# SerialConverter.net
KiCad netlist of a schematic drawn in Altium Designer
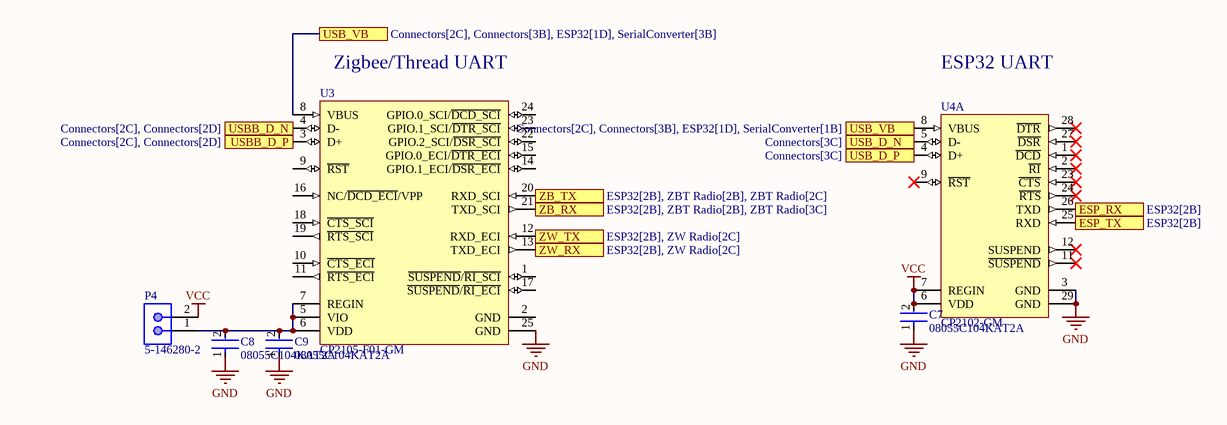
[diagram p0: SerialConverter.SchDoc]

(export (version "E")
  (design (tool "Eeschema 10.0.6"))
  (components
    (comp (ref "C7")
      (value "08055C104KAT2A")
      (footprint "FP-0805-L_2_01_0_2-W_1_25-IPC_C")
      (description "General Purpose Ceramic Capacitor, 0805, 100nF, 10%, X7R, 0.15, 50V")
      (fields (field (name "TOLERANCE") "10%") (field (name "VOLTAGE") "50V"))
      (libsource (lib "Altium Content Vault") (part "02cd4be3c70576c341d710602a673aa"))
    )
    (comp (ref "C8")
      (value "08055C104KAT2A")
      (footprint "FP-0805-L_2_01_0_2-W_1_25-IPC_C")
      (description "General Purpose Ceramic Capacitor, 0805, 100nF, 10%, X7R, 0.15, 50V")
      (fields (field (name "TOLERANCE") "10%") (field (name "VOLTAGE") "50V"))
      (libsource (lib "Altium Content Vault") (part "02cd4be3c70576c341d710602a673aa"))
    )
    (comp (ref "C9")
      (value "08055C104KAT2A")
      (footprint "FP-0805-L_2_01_0_2-W_1_25-IPC_C")
      (description "General Purpose Ceramic Capacitor, 0805, 100nF, 10%, X7R, 0.15, 50V")
      (fields (field (name "TOLERANCE") "10%") (field (name "VOLTAGE") "50V"))
      (libsource (lib "Altium Content Vault") (part "02cd4be3c70576c341d710602a673aa"))
    )
    (comp (ref "P4")
      (value "5-146280-2")
      (footprint "TECO-5-146280-2_V")
      (fields (field (name "MANUFACTURER") "TE Connectivity"))
      (libsource (lib "Altium Content Vault") (part "CN-1P-M-R2"))
    )
    (comp (ref "U3")
      (value "CP2105-F01-GM")
      (footprint "SLAB-QFN-24-2675x2675TP_N")
      (fields (field (name "MANUFACTURER") "Silicon Labs"))
      (libsource (lib "Altium Content Vault") (part "SLAB-CP2105-QFN-24-25"))
    )
    (comp (ref "U4")
      (value "CP2102-GM")
      (footprint "SLAB-QFN-28-3125x3125TP_N")
      (description "Single-Chip USB to UART Bridge, 1024 Bytes EEPROM, -40 to 85 degC, 28-pin QFN, Tube")
      (fields (field (name "MANUFACTURER") "Silicon Labs"))
      (libsource (lib "Altium Content Vault") (part "SLAB-CP210X-QFN-28-29"))
    )
  )
  (nets
    (net (code "1") (name "/ESP_RX") (class "Default")
      (node (ref "U4") (pin "26") (pinfunction "TXD_26") (pintype "output"))
    )
    (net (code "2") (name "/ESP_TX") (class "Default")
      (node (ref "U4") (pin "25") (pinfunction "RXD_25") (pintype "input"))
    )
    (net (code "3") (name "/USBB_D_N") (class "Default")
      (node (ref "U3") (pin "4") (pinfunction "D-_4") (pintype "bidirectional"))
    )
    (net (code "4") (name "/USBB_D_P") (class "Default")
      (node (ref "U3") (pin "3") (pinfunction "D+_3") (pintype "bidirectional"))
    )
    (net (code "5") (name "/USB_D_N") (class "Default")
      (node (ref "U4") (pin "5") (pinfunction "D-_5") (pintype "bidirectional"))
    )
    (net (code "6") (name "/USB_D_P") (class "Default")
      (node (ref "U4") (pin "4") (pinfunction "D+_4") (pintype "bidirectional"))
    )
    (net (code "7") (name "/USB_VB") (class "Default")
      (node (ref "U3") (pin "8") (pinfunction "VBUS_8") (pintype "input"))
      (node (ref "U4") (pin "8") (pinfunction "VBUS_8") (pintype "input"))
    )
    (net (code "8") (name "/ZB_RX") (class "Default")
      (node (ref "U3") (pin "21") (pinfunction "TXD_SCI_21") (pintype "output"))
    )
    (net (code "9") (name "/ZB_TX") (class "Default")
      (node (ref "U3") (pin "20") (pinfunction "RXD_SCI_20") (pintype "input"))
    )
    (net (code "10") (name "/ZW_RX") (class "Default")
      (node (ref "U3") (pin "13") (pinfunction "TXD_ECI_13") (pintype "output"))
    )
    (net (code "11") (name "/ZW_TX") (class "Default")
      (node (ref "U3") (pin "12") (pinfunction "RXD_ECI_12") (pintype "input"))
    )
    (net (code "12") (name "GND") (class "Default")
      (node (ref "C7") (pin "1") (pinfunction "1_1") (pintype "passive"))
      (node (ref "C8") (pin "1") (pinfunction "1_1") (pintype "passive"))
      (node (ref "C9") (pin "1") (pinfunction "1_1") (pintype "passive"))
      (node (ref "U3") (pin "25") (pinfunction "GND_25") (pintype "power_in"))
      (node (ref "U4") (pin "29") (pinfunction "GND_29") (pintype "power_in"))
      (node (ref "U4") (pin "3") (pinfunction "GND_3") (pintype "power_in"))
    )
    (net (code "13") (name "Net-(U3-REGIN)") (class "Default")
      (node (ref "C8") (pin "2") (pinfunction "2_2") (pintype "passive"))
      (node (ref "C9") (pin "2") (pinfunction "2_2") (pintype "passive"))
      (node (ref "P4") (pin "1") (pinfunction "1_1") (pintype "passive"))
      (node (ref "U3") (pin "5") (pinfunction "VIO_5") (pintype "power_in"))
      (node (ref "U3") (pin "6") (pinfunction "VDD_6") (pintype "power_in"))
      (node (ref "U3") (pin "7") (pinfunction "REGIN_7") (pintype "power_in"))
    )
    (net (code "14") (name "VCC") (class "Default")
      (node (ref "C7") (pin "2") (pinfunction "2_2") (pintype "passive"))
      (node (ref "P4") (pin "2") (pinfunction "2_2") (pintype "passive"))
      (node (ref "U4") (pin "6") (pinfunction "VDD_6") (pintype "power_in"))
      (node (ref "U4") (pin "7") (pinfunction "REGIN_7") (pintype "power_in"))
    )
    (net (code "15") (name "unconnected-(U3-GND-Pad2)") (class "Default")
      (node (ref "U3") (pin "2") (pinfunction "GND_2") (pintype "power_in"))
    )
    (net (code "16") (name "unconnected-(U3-GPIO.0_ECI{slash}~{DTR_ECI}-Pad15)") (class "Default")
      (node (ref "U3") (pin "15") (pinfunction "GPIO.0_ECI/~{DTR_ECI}_15") (pintype "bidirectional"))
    )
    (net (code "17") (name "unconnected-(U3-GPIO.0_SCI{slash}~{DCD_SCI}-Pad24)") (class "Default")
      (node (ref "U3") (pin "24") (pinfunction "GPIO.0_SCI/~{DCD_SCI}_24") (pintype "bidirectional"))
    )
    (net (code "18") (name "unconnected-(U3-GPIO.1_ECI{slash}~{DSR_ECI}-Pad14)") (class "Default")
      (node (ref "U3") (pin "14") (pinfunction "GPIO.1_ECI/~{DSR_ECI}_14") (pintype "bidirectional"))
    )
    (net (code "19") (name "unconnected-(U3-GPIO.1_SCI{slash}~{DTR_SCI}-Pad23)") (class "Default")
      (node (ref "U3") (pin "23") (pinfunction "GPIO.1_SCI/~{DTR_SCI}_23") (pintype "bidirectional"))
    )
    (net (code "20") (name "unconnected-(U3-GPIO.2_SCI{slash}~{DSR_SCI}-Pad22)") (class "Default")
      (node (ref "U3") (pin "22") (pinfunction "GPIO.2_SCI/~{DSR_SCI}_22") (pintype "bidirectional"))
    )
    (net (code "21") (name "unconnected-(U3-NC{slash}~{DCD_ECI}{slash}VPP-Pad16)") (class "Default")
      (node (ref "U3") (pin "16") (pinfunction "NC/~{DCD_ECI}/VPP_16") (pintype "input"))
    )
    (net (code "22") (name "unconnected-(U3-~{CTS_ECI}-Pad10)") (class "Default")
      (node (ref "U3") (pin "10") (pinfunction "~{CTS_ECI}_10") (pintype "input"))
    )
    (net (code "23") (name "unconnected-(U3-~{CTS_SCI}-Pad18)") (class "Default")
      (node (ref "U3") (pin "18") (pinfunction "~{CTS_SCI}_18") (pintype "input"))
    )
    (net (code "24") (name "unconnected-(U3-~{RST}-Pad9)") (class "Default")
      (node (ref "U3") (pin "9") (pinfunction "~{RST}_9") (pintype "bidirectional"))
    )
    (net (code "25") (name "unconnected-(U3-~{RTS_ECI}-Pad11)") (class "Default")
      (node (ref "U3") (pin "11") (pinfunction "~{RTS_ECI}_11") (pintype "output"))
    )
    (net (code "26") (name "unconnected-(U3-~{RTS_SCI}-Pad19)") (class "Default")
      (node (ref "U3") (pin "19") (pinfunction "~{RTS_SCI}_19") (pintype "output"))
    )
    (net (code "27") (name "unconnected-(U3-~{SUSPEND}{slash}~{RI_ECI}-Pad17)") (class "Default")
      (node (ref "U3") (pin "17") (pinfunction "~{SUSPEND}/~{RI_ECI}_17") (pintype "bidirectional"))
    )
    (net (code "28") (name "unconnected-(U3-~{SUSPEND}{slash}~{RI_SCI}-Pad1)") (class "Default")
      (node (ref "U3") (pin "1") (pinfunction "~{SUSPEND}/~{RI_SCI}_1") (pintype "bidirectional"))
    )
    (net (code "29") (name "unconnected-(U4A-SUSPEND-Pad12)") (class "Default")
      (node (ref "U4") (pin "12") (pinfunction "SUSPEND_12") (pintype "output+no_connect"))
    )
    (net (code "30") (name "unconnected-(U4A-~{CTS}-Pad23)") (class "Default")
      (node (ref "U4") (pin "23") (pinfunction "~{CTS}_23") (pintype "input+no_connect"))
    )
    (net (code "31") (name "unconnected-(U4A-~{DCD}-Pad1)") (class "Default")
      (node (ref "U4") (pin "1") (pinfunction "~{DCD}_1") (pintype "input+no_connect"))
    )
    (net (code "32") (name "unconnected-(U4A-~{DSR}-Pad27)") (class "Default")
      (node (ref "U4") (pin "27") (pinfunction "~{DSR}_27") (pintype "input+no_connect"))
    )
    (net (code "33") (name "unconnected-(U4A-~{DTR}-Pad28)") (class "Default")
      (node (ref "U4") (pin "28") (pinfunction "~{DTR}_28") (pintype "output+no_connect"))
    )
    (net (code "34") (name "unconnected-(U4A-~{RI}-Pad2)") (class "Default")
      (node (ref "U4") (pin "2") (pinfunction "~{RI}_2") (pintype "input+no_connect"))
    )
    (net (code "35") (name "unconnected-(U4A-~{RST}-Pad9)") (class "Default")
      (node (ref "U4") (pin "9") (pinfunction "~{RST}_9") (pintype "bidirectional+no_connect"))
    )
    (net (code "36") (name "unconnected-(U4A-~{RTS}-Pad24)") (class "Default")
      (node (ref "U4") (pin "24") (pinfunction "~{RTS}_24") (pintype "output+no_connect"))
    )
    (net (code "37") (name "unconnected-(U4A-~{SUSPEND}-Pad11)") (class "Default")
      (node (ref "U4") (pin "11") (pinfunction "~{SUSPEND}_11") (pintype "output+no_connect"))
    )
  )
)
